# MySens-GWeasySensRS485-V01-060.net
KiCad netlist of a schematic drawn in EAGLE
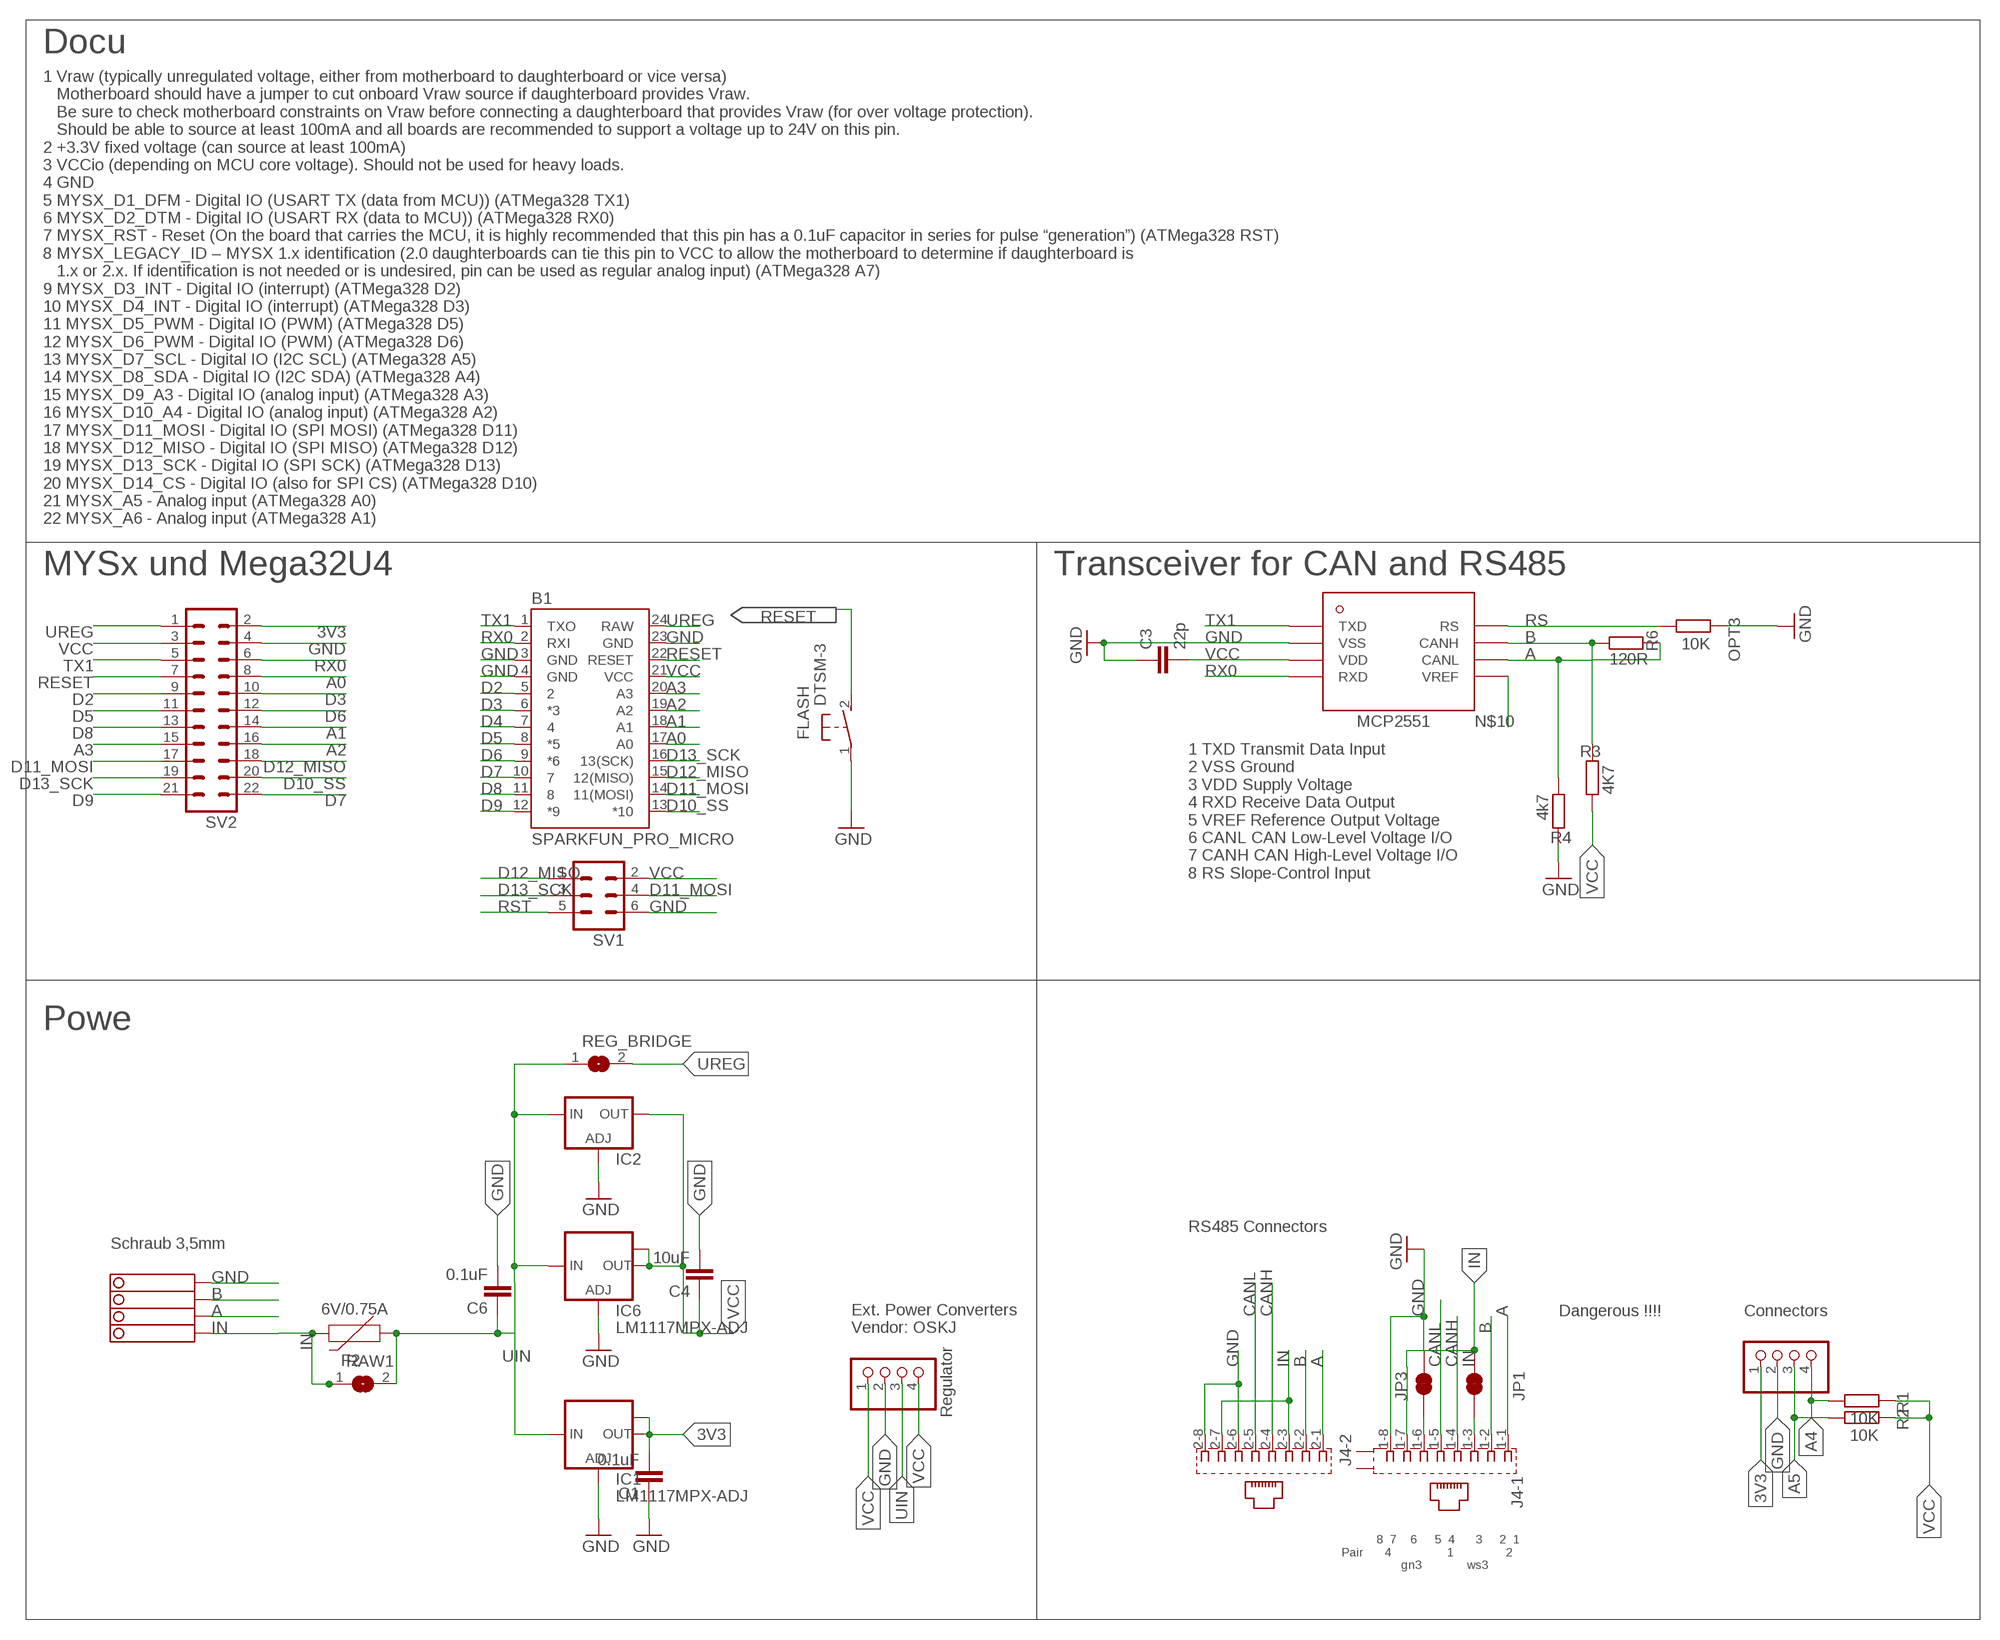
[diagram p0: schematic, sheet 1]

(export (version "E")
  (design (tool "Eeschema 10.0.6"))
  (components
    (comp (ref "B1")
      (value "SPARKFUN_PRO_MICRO")
      (footprint "eagle-import:SPARKFUN_PRO_MICRO")
      (libsource (lib "eagle-import") (part "SPARKFUN_PRO_MICRO"))
    )
    (comp (ref "C1")
      (value "0.1uF")
      (footprint "eagle-import:C1206")
      (libsource (lib "eagle-import") (part "C-EUC1206"))
    )
    (comp (ref "C3")
      (value "22p")
      (footprint "eagle-import:C0805")
      (libsource (lib "eagle-import") (part "C-EUC0805"))
    )
    (comp (ref "C4")
      (value "10uF")
      (footprint "eagle-import:C1210")
      (libsource (lib "eagle-import") (part "C-EUC1210"))
    )
    (comp (ref "C6")
      (value "0.1uF")
      (footprint "eagle-import:C1206")
      (libsource (lib "eagle-import") (part "C-EUC1206"))
    )
    (comp (ref "F2")
      (value "6V/0.75A")
      (footprint "eagle-import:1206")
      (libsource (lib "eagle-import") (part "PPTC_THREE-QUARTER-AMP"))
    )
    (comp (ref "FLASH")
      (value "DTSM-3")
      (footprint "eagle-import:DTSM-3")
      (libsource (lib "eagle-import") (part "DTSM-3"))
    )
    (comp (ref "I2C")
      (value "PINHD-1X04_2.54-S")
      (footprint "eagle-import:1X04-S")
      (libsource (lib "eagle-import") (part "PINHD-1X04_2.54-S"))
    )
    (comp (ref "IC1")
      (value "LM1117MPX-ADJ")
      (footprint "eagle-import:SOT223")
      (libsource (lib "eagle-import") (part "LM1117MPX-ADJ"))
    )
    (comp (ref "IC2")
      (value "LD117ADT50TR")
      (footprint "eagle-import:DPACK")
      (libsource (lib "eagle-import") (part "LD117A?DT50TR"))
    )
    (comp (ref "IC6")
      (value "LM1117MPX-ADJ")
      (footprint "eagle-import:SOT223")
      (libsource (lib "eagle-import") (part "LM1117MPX-ADJ"))
    )
    (comp (ref "J4")
      (value "RJ45_2X_S")
      (footprint "eagle-import:RJ45_2X_S")
      (libsource (lib "eagle-import") (part "RJ45_2X_S"))
    )
    (comp (ref "JP1")
      (value "JUMPER-SMT_2_NC_TRACE_SILK")
      (footprint "eagle-import:SMT-JUMPER_2_NC_TRACE_SILK")
      (libsource (lib "eagle-import") (part "JUMPER-SMT_2_NC_TRACE_SILK"))
    )
    (comp (ref "JP3")
      (value "JUMPER-SMT_2_NC_TRACE_SILK")
      (footprint "eagle-import:SMT-JUMPER_2_NC_TRACE_SILK")
      (libsource (lib "eagle-import") (part "JUMPER-SMT_2_NC_TRACE_SILK"))
    )
    (comp (ref "OPT3")
      (value "10K")
      (footprint "eagle-import:R0805")
      (libsource (lib "eagle-import") (part "R-EU_R0805"))
    )
    (comp (ref "R1")
      (value "10K")
      (footprint "eagle-import:R0805")
      (libsource (lib "eagle-import") (part "R-EU_R0805"))
    )
    (comp (ref "R2")
      (value "10K")
      (footprint "eagle-import:R0805")
      (libsource (lib "eagle-import") (part "R-EU_R0805"))
    )
    (comp (ref "R3")
      (value "4K7")
      (footprint "eagle-import:R0805")
      (libsource (lib "eagle-import") (part "R-EU_R0805"))
    )
    (comp (ref "R4")
      (value "4k7")
      (footprint "eagle-import:R0805")
      (libsource (lib "eagle-import") (part "R-EU_R0805"))
    )
    (comp (ref "R6")
      (value "120R")
      (footprint "eagle-import:R0805")
      (libsource (lib "eagle-import") (part "R-EU_R0805"))
    )
    (comp (ref "RAW1")
      (value "SJ")
      (footprint "eagle-import:SJ")
      (libsource (lib "eagle-import") (part "SJ"))
    )
    (comp (ref "REG_BRIDGE")
      (value "SJ")
      (footprint "eagle-import:SJ")
      (libsource (lib "eagle-import") (part "SJ"))
    )
    (comp (ref "STEPDWN")
      (value "PINHD-1X04_2.54-S")
      (footprint "eagle-import:1X04-S")
      (libsource (lib "eagle-import") (part "PINHD-1X04_2.54-S"))
    )
    (comp (ref "SV1")
      (value "MA03-2")
      (footprint "eagle-import:MA03-2")
      (libsource (lib "eagle-import") (part "MA03-2"))
    )
    (comp (ref "SV2")
      (value "MA11-2")
      (footprint "eagle-import:MA11-2")
      (libsource (lib "eagle-import") (part "MA11-2"))
    )
    (comp (ref "U$1")
      (value "MCP2551")
      (footprint "eagle-import:SOIC-8")
      (libsource (lib "eagle-import") (part "MCP2551"))
    )
    (comp (ref "X4")
      (value "1751264")
      (footprint "eagle-import:1751264")
      (libsource (lib "eagle-import") (part "1751264"))
    )
  )
  (nets
    (net (code "1") (name "/A") (class "Default")
      (node (ref "J4") (pin "1-1") (pinfunction "1_1-1") (pintype "passive"))
      (node (ref "J4") (pin "2-1") (pinfunction "1_2-1") (pintype "passive"))
      (node (ref "R4") (pin "1") (pinfunction "1_1") (pintype "passive"))
      (node (ref "R6") (pin "2") (pinfunction "2_2") (pintype "passive"))
      (node (ref "U$1") (pin "CANL") (pinfunction "CANL_CANL") (pintype "bidirectional"))
      (node (ref "X4") (pin "2") (pinfunction "K_2") (pintype "passive"))
    )
    (net (code "2") (name "/A0") (class "Default")
      (node (ref "B1") (pin "17") (pinfunction "A0_17") (pintype "bidirectional"))
      (node (ref "SV2") (pin "8") (pinfunction "8_8") (pintype "passive"))
    )
    (net (code "3") (name "/A1") (class "Default")
      (node (ref "B1") (pin "18") (pinfunction "A1_18") (pintype "bidirectional"))
      (node (ref "SV2") (pin "14") (pinfunction "14_14") (pintype "passive"))
    )
    (net (code "4") (name "/A2") (class "Default")
      (node (ref "B1") (pin "19") (pinfunction "A2_19") (pintype "bidirectional"))
      (node (ref "SV2") (pin "16") (pinfunction "16_16") (pintype "passive"))
    )
    (net (code "5") (name "/A3") (class "Default")
      (node (ref "B1") (pin "20") (pinfunction "A3_20") (pintype "bidirectional"))
      (node (ref "SV2") (pin "15") (pinfunction "15_15") (pintype "passive"))
    )
    (net (code "6") (name "/B") (class "Default")
      (node (ref "J4") (pin "1-2") (pinfunction "2_1-2") (pintype "passive"))
      (node (ref "J4") (pin "2-2") (pinfunction "2_2-2") (pintype "passive"))
      (node (ref "R3") (pin "2") (pinfunction "2_2") (pintype "passive"))
      (node (ref "R6") (pin "1") (pinfunction "1_1") (pintype "passive"))
      (node (ref "U$1") (pin "CANH") (pinfunction "CANH_CANH") (pintype "bidirectional"))
      (node (ref "X4") (pin "3") (pinfunction "K_3") (pintype "passive"))
    )
    (net (code "7") (name "/CANH") (class "Default")
      (node (ref "J4") (pin "1-4") (pinfunction "4_1-4") (pintype "passive"))
      (node (ref "J4") (pin "2-4") (pinfunction "4_2-4") (pintype "passive"))
    )
    (net (code "8") (name "/CANL") (class "Default")
      (node (ref "J4") (pin "1-5") (pinfunction "5_1-5") (pintype "passive"))
      (node (ref "J4") (pin "2-5") (pinfunction "5_2-5") (pintype "passive"))
    )
    (net (code "9") (name "/D2") (class "Default")
      (node (ref "B1") (pin "5") (pinfunction "2_5") (pintype "bidirectional"))
      (node (ref "SV2") (pin "9") (pinfunction "9_9") (pintype "passive"))
    )
    (net (code "10") (name "/D3") (class "Default")
      (node (ref "B1") (pin "6") (pinfunction "*3_6") (pintype "bidirectional"))
      (node (ref "SV2") (pin "10") (pinfunction "10_10") (pintype "passive"))
    )
    (net (code "11") (name "/D4") (class "Default")
      (node (ref "B1") (pin "7") (pinfunction "4_7") (pintype "bidirectional"))
    )
    (net (code "12") (name "/D5") (class "Default")
      (node (ref "B1") (pin "8") (pinfunction "*5_8") (pintype "bidirectional"))
      (node (ref "SV2") (pin "11") (pinfunction "11_11") (pintype "passive"))
    )
    (net (code "13") (name "/D6") (class "Default")
      (node (ref "B1") (pin "9") (pinfunction "*6_9") (pintype "bidirectional"))
      (node (ref "SV2") (pin "12") (pinfunction "12_12") (pintype "passive"))
    )
    (net (code "14") (name "/D7") (class "Default")
      (node (ref "B1") (pin "10") (pinfunction "7_10") (pintype "bidirectional"))
      (node (ref "SV2") (pin "22") (pinfunction "22_22") (pintype "passive"))
    )
    (net (code "15") (name "/D8") (class "Default")
      (node (ref "B1") (pin "11") (pinfunction "8_11") (pintype "bidirectional"))
      (node (ref "SV2") (pin "13") (pinfunction "13_13") (pintype "passive"))
    )
    (net (code "16") (name "/D9") (class "Default")
      (node (ref "B1") (pin "12") (pinfunction "*9_12") (pintype "bidirectional"))
      (node (ref "SV2") (pin "21") (pinfunction "21_21") (pintype "passive"))
    )
    (net (code "17") (name "/D10_SS") (class "Default")
      (node (ref "B1") (pin "13") (pinfunction "*10_13") (pintype "bidirectional"))
      (node (ref "SV2") (pin "20") (pinfunction "20_20") (pintype "passive"))
    )
    (net (code "18") (name "/D11_MOSI") (class "Default")
      (node (ref "B1") (pin "14") (pinfunction "11(MOSI)_14") (pintype "bidirectional"))
      (node (ref "SV1") (pin "4") (pinfunction "4_4") (pintype "passive"))
      (node (ref "SV2") (pin "17") (pinfunction "17_17") (pintype "passive"))
    )
    (net (code "19") (name "/D12_MISO") (class "Default")
      (node (ref "B1") (pin "15") (pinfunction "12(MISO)_15") (pintype "bidirectional"))
      (node (ref "SV1") (pin "1") (pinfunction "1_1") (pintype "passive"))
      (node (ref "SV2") (pin "18") (pinfunction "18_18") (pintype "passive"))
    )
    (net (code "20") (name "/D13_SCK") (class "Default")
      (node (ref "B1") (pin "16") (pinfunction "13(SCK)_16") (pintype "bidirectional"))
      (node (ref "SV1") (pin "3") (pinfunction "3_3") (pintype "passive"))
      (node (ref "SV2") (pin "19") (pinfunction "19_19") (pintype "passive"))
    )
    (net (code "21") (name "/N$10") (class "Default")
      (node (ref "U$1") (pin "VREF") (pinfunction "VREF_VREF") (pintype "bidirectional"))
    )
    (net (code "22") (name "/RESET") (class "Default")
      (node (ref "B1") (pin "22") (pinfunction "RESET_22") (pintype "bidirectional"))
      (node (ref "FLASH") (pin "2") (pinfunction "2_2") (pintype "passive"))
      (node (ref "SV2") (pin "7") (pinfunction "7_7") (pintype "passive"))
    )
    (net (code "23") (name "/RS") (class "Default")
      (node (ref "OPT3") (pin "2") (pinfunction "2_2") (pintype "passive"))
      (node (ref "U$1") (pin "RS") (pinfunction "RS_RS") (pintype "bidirectional"))
    )
    (net (code "24") (name "/RST") (class "Default")
      (node (ref "SV1") (pin "5") (pinfunction "5_5") (pintype "passive"))
    )
    (net (code "25") (name "/RX0") (class "Default")
      (node (ref "B1") (pin "2") (pinfunction "RXI_2") (pintype "bidirectional"))
      (node (ref "SV2") (pin "6") (pinfunction "6_6") (pintype "passive"))
      (node (ref "U$1") (pin "RXD") (pinfunction "RXD_RXD") (pintype "bidirectional"))
    )
    (net (code "26") (name "/TX1") (class "Default")
      (node (ref "B1") (pin "1") (pinfunction "TXO_1") (pintype "bidirectional"))
      (node (ref "SV2") (pin "5") (pinfunction "5_5") (pintype "passive"))
      (node (ref "U$1") (pin "TXD") (pinfunction "TXD_TXD") (pintype "bidirectional"))
    )
    (net (code "27") (name "3V3") (class "Default")
      (node (ref "C1") (pin "2") (pinfunction "2_2") (pintype "passive"))
      (node (ref "I2C") (pin "1") (pinfunction "1_1") (pintype "passive"))
      (node (ref "IC1") (pin "2") (pinfunction "OUT_2") (pintype "passive"))
      (node (ref "IC1") (pin "TAB") (pinfunction "OUT1_TAB") (pintype "passive"))
      (node (ref "SV2") (pin "2") (pinfunction "2_2") (pintype "passive"))
    )
    (net (code "28") (name "A4") (class "Default")
      (node (ref "I2C") (pin "4") (pinfunction "4_4") (pintype "passive"))
      (node (ref "R1") (pin "2") (pinfunction "2_2") (pintype "passive"))
    )
    (net (code "29") (name "A5") (class "Default")
      (node (ref "I2C") (pin "3") (pinfunction "3_3") (pintype "passive"))
      (node (ref "R2") (pin "2") (pinfunction "2_2") (pintype "passive"))
    )
    (net (code "30") (name "GND") (class "Default")
      (node (ref "B1") (pin "23") (pinfunction "GND_23") (pintype "power_in"))
      (node (ref "B1") (pin "3") (pinfunction "GND_3") (pintype "power_in"))
      (node (ref "B1") (pin "4") (pinfunction "GND_4") (pintype "power_in"))
      (node (ref "C1") (pin "1") (pinfunction "1_1") (pintype "passive"))
      (node (ref "C3") (pin "1") (pinfunction "1_1") (pintype "passive"))
      (node (ref "C4") (pin "2") (pinfunction "2_2") (pintype "passive"))
      (node (ref "C6") (pin "2") (pinfunction "2_2") (pintype "passive"))
      (node (ref "FLASH") (pin "1") (pinfunction "1_1") (pintype "passive"))
      (node (ref "I2C") (pin "2") (pinfunction "2_2") (pintype "passive"))
      (node (ref "IC1") (pin "1") (pinfunction "ADJ_1") (pintype "input"))
      (node (ref "IC2") (pin "1") (pinfunction "ADJ_1") (pintype "input"))
      (node (ref "IC6") (pin "1") (pinfunction "ADJ_1") (pintype "input"))
      (node (ref "J4") (pin "1-8") (pinfunction "8_1-8") (pintype "passive"))
      (node (ref "J4") (pin "2-6") (pinfunction "6_2-6") (pintype "passive"))
      (node (ref "J4") (pin "2-8") (pinfunction "8_2-8") (pintype "passive"))
      (node (ref "JP3") (pin "2") (pinfunction "2_2") (pintype "passive"))
      (node (ref "OPT3") (pin "1") (pinfunction "1_1") (pintype "passive"))
      (node (ref "R4") (pin "2") (pinfunction "2_2") (pintype "passive"))
      (node (ref "STEPDWN") (pin "2") (pinfunction "2_2") (pintype "passive"))
      (node (ref "SV1") (pin "6") (pinfunction "6_6") (pintype "passive"))
      (node (ref "SV2") (pin "4") (pinfunction "4_4") (pintype "passive"))
      (node (ref "U$1") (pin "VSS") (pinfunction "VSS_VSS") (pintype "bidirectional"))
      (node (ref "X4") (pin "4") (pinfunction "K_4") (pintype "passive"))
    )
    (net (code "31") (name "IN") (class "Default")
      (node (ref "F2") (pin "2") (pinfunction "2_2") (pintype "bidirectional"))
      (node (ref "J4") (pin "1-7") (pinfunction "7_1-7") (pintype "passive"))
      (node (ref "J4") (pin "2-3") (pinfunction "3_2-3") (pintype "passive"))
      (node (ref "J4") (pin "2-7") (pinfunction "7_2-7") (pintype "passive"))
      (node (ref "JP1") (pin "2") (pinfunction "2_2") (pintype "passive"))
      (node (ref "RAW1") (pin "1") (pinfunction "1_1") (pintype "passive"))
      (node (ref "X4") (pin "1") (pinfunction "K_1") (pintype "passive"))
    )
    (net (code "32") (name "Net-(J4A-3)") (class "Default")
      (node (ref "J4") (pin "1-3") (pinfunction "3_1-3") (pintype "passive"))
      (node (ref "JP1") (pin "1") (pinfunction "1_1") (pintype "passive"))
    )
    (net (code "33") (name "Net-(J4A-6)") (class "Default")
      (node (ref "J4") (pin "1-6") (pinfunction "6_1-6") (pintype "passive"))
      (node (ref "JP3") (pin "1") (pinfunction "1_1") (pintype "passive"))
    )
    (net (code "34") (name "UIN") (class "Default")
      (node (ref "C6") (pin "1") (pinfunction "1_1") (pintype "passive"))
      (node (ref "F2") (pin "1") (pinfunction "1_1") (pintype "bidirectional"))
      (node (ref "IC1") (pin "3") (pinfunction "IN_3") (pintype "input"))
      (node (ref "IC2") (pin "3") (pinfunction "IN_3") (pintype "input"))
      (node (ref "IC6") (pin "3") (pinfunction "IN_3") (pintype "input"))
      (node (ref "RAW1") (pin "2") (pinfunction "2_2") (pintype "passive"))
      (node (ref "REG_BRIDGE") (pin "1") (pinfunction "1_1") (pintype "passive"))
      (node (ref "STEPDWN") (pin "3") (pinfunction "3_3") (pintype "passive"))
    )
    (net (code "35") (name "UREG") (class "Default")
      (node (ref "B1") (pin "24") (pinfunction "RAW_24") (pintype "power_in"))
      (node (ref "REG_BRIDGE") (pin "2") (pinfunction "2_2") (pintype "passive"))
      (node (ref "SV2") (pin "1") (pinfunction "1_1") (pintype "passive"))
    )
    (net (code "36") (name "VCC") (class "Default")
      (node (ref "B1") (pin "21") (pinfunction "VCC_21") (pintype "power_in"))
      (node (ref "C3") (pin "2") (pinfunction "2_2") (pintype "passive"))
      (node (ref "C4") (pin "1") (pinfunction "1_1") (pintype "passive"))
      (node (ref "IC2") (pin "4") (pinfunction "OUT_4") (pintype "passive"))
      (node (ref "IC6") (pin "2") (pinfunction "OUT_2") (pintype "passive"))
      (node (ref "IC6") (pin "TAB") (pinfunction "OUT1_TAB") (pintype "passive"))
      (node (ref "R1") (pin "1") (pinfunction "1_1") (pintype "passive"))
      (node (ref "R2") (pin "1") (pinfunction "1_1") (pintype "passive"))
      (node (ref "R3") (pin "1") (pinfunction "1_1") (pintype "passive"))
      (node (ref "STEPDWN") (pin "1") (pinfunction "1_1") (pintype "passive"))
      (node (ref "STEPDWN") (pin "4") (pinfunction "4_4") (pintype "passive"))
      (node (ref "SV1") (pin "2") (pinfunction "2_2") (pintype "passive"))
      (node (ref "SV2") (pin "3") (pinfunction "3_3") (pintype "passive"))
      (node (ref "U$1") (pin "VDD") (pinfunction "VDD_VDD") (pintype "bidirectional"))
    )
    (net (code "37") (name "unconnected-(J4A-S1-PadG3)") (class "Default")
      (node (ref "J4") (pin "G3") (pinfunction "S1_G3") (pintype "passive"))
    )
    (net (code "38") (name "unconnected-(J4A-S2-PadG1)") (class "Default")
      (node (ref "J4") (pin "G1") (pinfunction "S2_G1") (pintype "passive"))
    )
  )
)
